# Main.net
KiCad netlist of a schematic drawn in Altium Designer
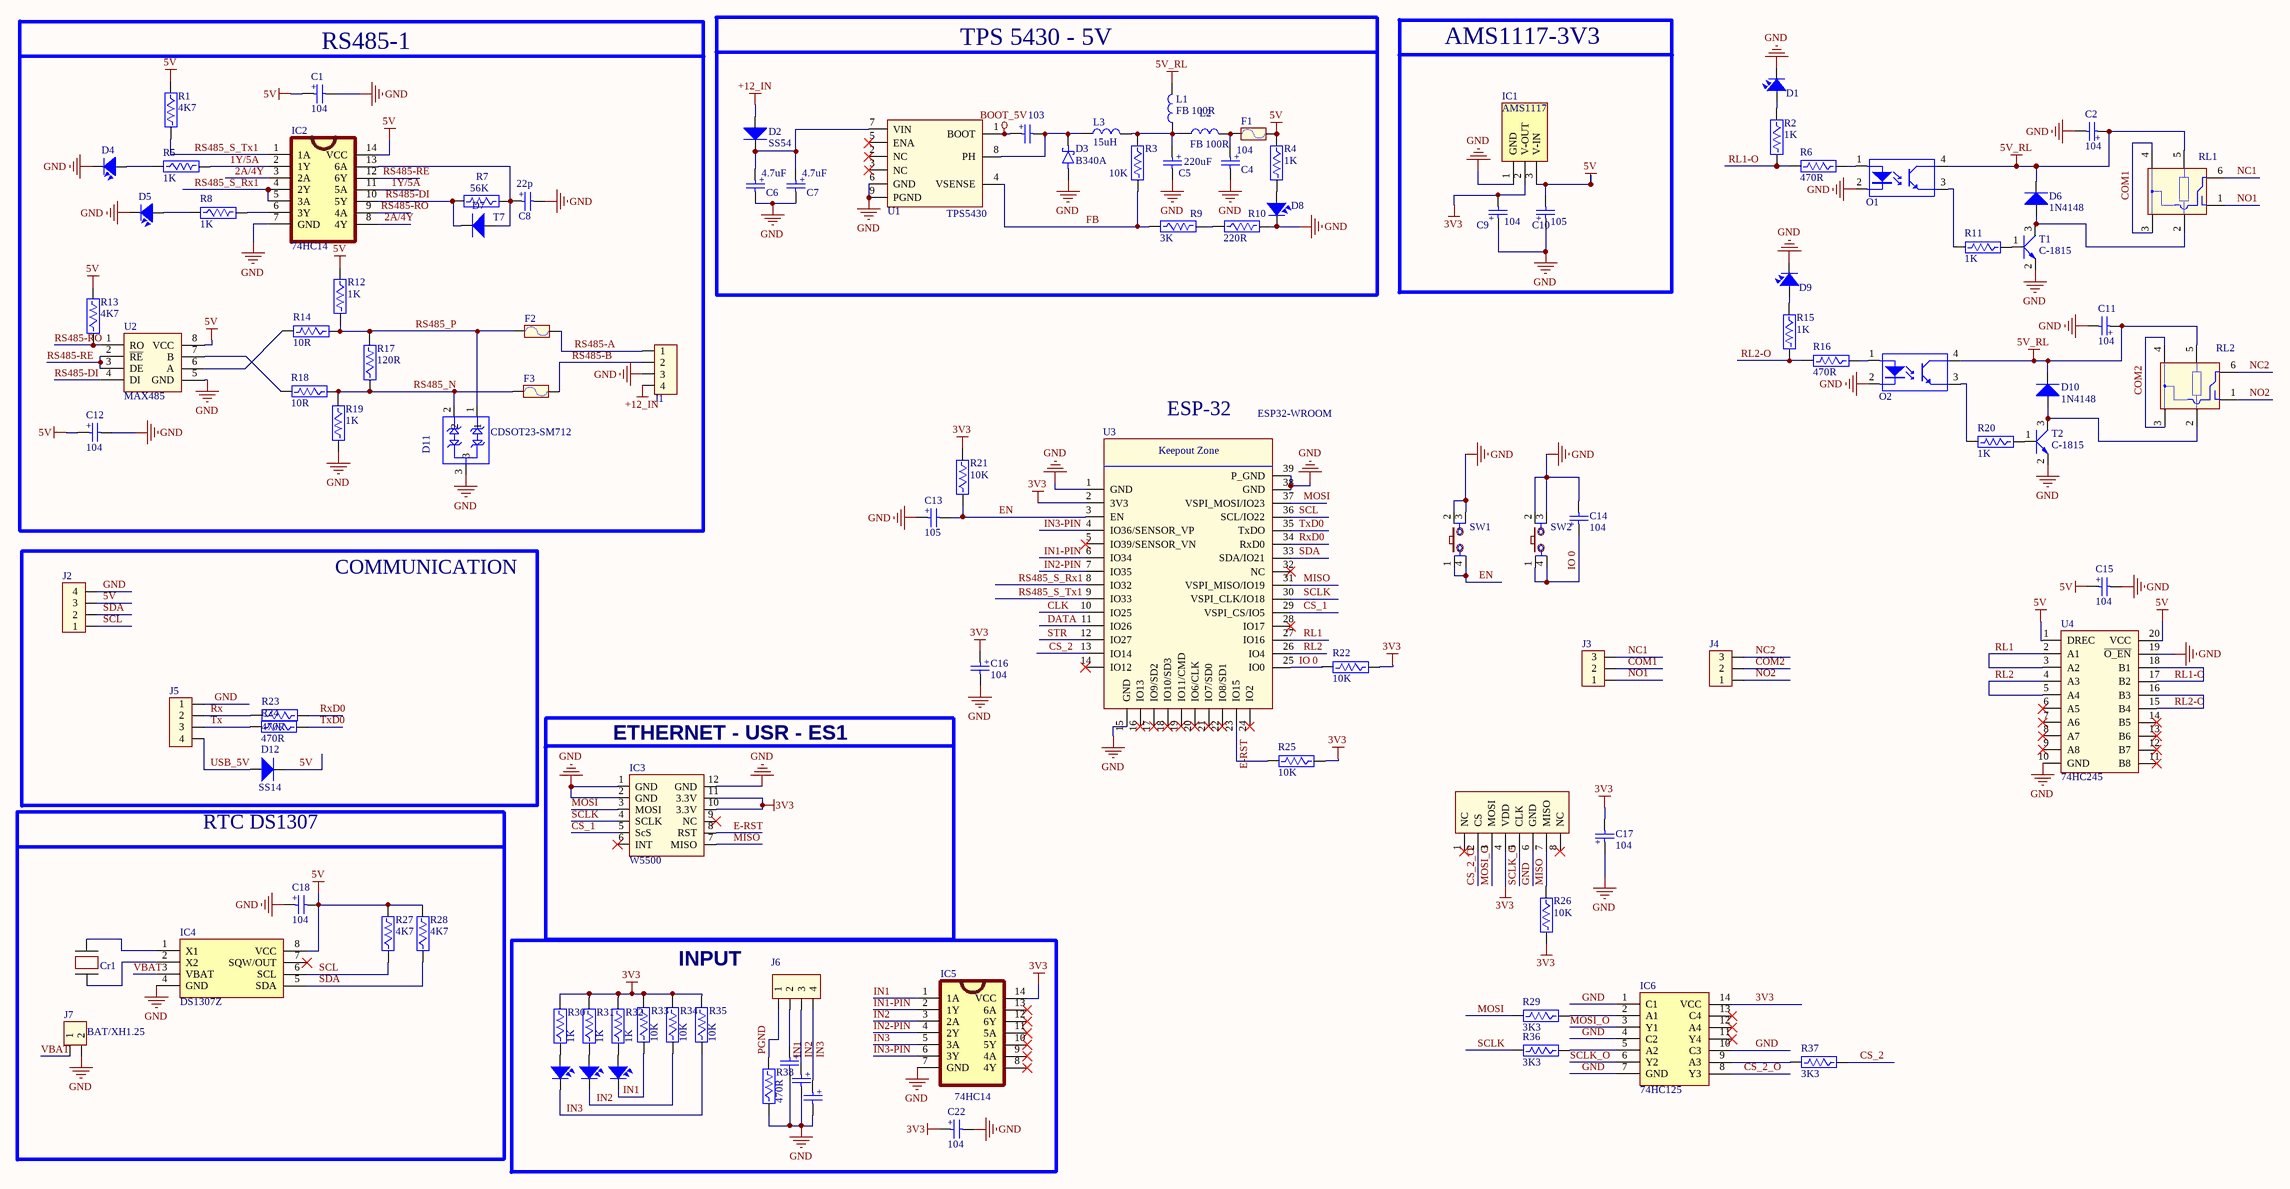
[diagram p0: Main.SchDoc]

(export (version "E")
  (design (tool "Eeschema 10.0.6"))
  (components
    (comp (ref "C1") (value "104") (footprint "CAP 0805") (libsource (lib "Silver Sch") (part "Capacitor")))
    (comp (ref "C2") (value "104") (footprint "CAP 0805") (libsource (lib "Silver Sch") (part "Capacitor")))
    (comp (ref "C3") (value "103") (footprint "CAP 0805") (libsource (lib "Silver Sch") (part "Capacitor")))
    (comp (ref "C4") (value "104") (footprint "CAP 0805") (libsource (lib "Silver Sch") (part "Capacitor")))
    (comp (ref "C5")
      (value "220uF")
      (footprint "Capacitor 6x11")
      (libsource (lib "Silver Sch") (part "Capacitor"))
    )
    (comp (ref "C6") (value "4.7uF") (footprint "CAP 0805") (libsource (lib "Silver Sch") (part "Capacitor")))
    (comp (ref "C7") (value "4.7uF") (footprint "CAP 0805") (libsource (lib "Silver Sch") (part "Capacitor")))
    (comp (ref "C8") (value "22p") (footprint "CAP 0805") (libsource (lib "Silver Sch") (part "Capacitor")))
    (comp (ref "C9") (value "104") (footprint "CAP 0805") (libsource (lib "Silver Sch") (part "Capacitor")))
    (comp (ref "C10") (value "105") (footprint "CAP 0805") (libsource (lib "Silver Sch") (part "Capacitor")))
    (comp (ref "C11") (value "104") (footprint "CAP 0805") (libsource (lib "Silver Sch") (part "Capacitor")))
    (comp (ref "C12") (value "104") (footprint "CAP 0805") (libsource (lib "Silver Sch") (part "Capacitor")))
    (comp (ref "C13") (value "105") (footprint "CAP 0805") (libsource (lib "Silver Sch") (part "Capacitor")))
    (comp (ref "C14") (value "104") (footprint "CAP 0805") (libsource (lib "Silver Sch") (part "Capacitor")))
    (comp (ref "C15") (value "104") (footprint "CAP 0805") (libsource (lib "Silver Sch") (part "Capacitor")))
    (comp (ref "C16") (value "104") (footprint "CAP 0805") (libsource (lib "Silver Sch") (part "Capacitor")))
    (comp (ref "C17") (value "104") (footprint "CAP 0805") (libsource (lib "Silver Sch") (part "Capacitor")))
    (comp (ref "C18") (value "104") (footprint "CAP 0805") (libsource (lib "Silver Sch") (part "Capacitor")))
    (comp (ref "C19") (value "104") (footprint "CAP 0805") (libsource (lib "Silver Sch") (part "Capacitor")))
    (comp (ref "C20") (value "104") (footprint "CAP 0805") (libsource (lib "Silver Sch") (part "Capacitor")))
    (comp (ref "C21") (value "104") (footprint "CAP 0805") (libsource (lib "Silver Sch") (part "Capacitor")))
    (comp (ref "C22") (value "104") (footprint "CAP 0805") (libsource (lib "Silver Sch") (part "Capacitor")))
    (comp (ref "Cr1")
      (value "FC135")
      (footprint "FC135327680KAAG0")
      (libsource (lib "Silver Sch") (part "Crystal"))
    )
    (comp (ref "D1")
      (value "LED RED 0805")
      (footprint "LED SMD 0805")
      (libsource (lib "Silver Sch") (part "Led Smd"))
    )
    (comp (ref "D2") (value "SS54") (footprint "Diode SMB") (libsource (lib "Silver Sch") (part "Diode")))
    (comp (ref "D3")
      (value "B340A")
      (footprint "Diode Schotky")
      (libsource (lib "Silver Sch") (part "Diode schottky"))
    )
    (comp (ref "D4")
      (value "LED RED 0805")
      (footprint "LED SMD 0805")
      (libsource (lib "Silver Sch") (part "Led Smd"))
    )
    (comp (ref "D5")
      (value "LED RED 0805")
      (footprint "LED SMD 0805")
      (libsource (lib "Silver Sch") (part "Led Smd"))
    )
    (comp (ref "D6") (value "1N4148") (footprint "1N4848") (libsource (lib "Silver Sch") (part "1N4148")))
    (comp (ref "D7") (value "T7") (footprint "Diode SMD") (libsource (lib "Silver Sch") (part "Diode")))
    (comp (ref "D8")
      (value "LED RED 0805")
      (footprint "LED SMD 0805")
      (libsource (lib "Silver Sch") (part "Led Smd"))
    )
    (comp (ref "D9")
      (value "LED RED 0805")
      (footprint "LED SMD 0805")
      (libsource (lib "Silver Sch") (part "Led Smd"))
    )
    (comp (ref "D10") (value "1N4148") (footprint "1N4848") (libsource (lib "Silver Sch") (part "1N4148")))
    (comp (ref "D11")
      (value "SM712")
      (footprint "SOT-23-3")
      (description "TVS-DIODE;BIR-DIR,DUAL,400W,7.5V,SOT23,CDSOT23-SM712")
      (fields (field (name "M1_VALUE") "CDSOT23-SM712"))
      (libsource (lib "NS16-001650") (part "TVS-CDSOT23-SM712"))
    )
    (comp (ref "D12") (value "SS14") (footprint "Diode SMB") (libsource (lib "Silver Sch") (part "Diode")))
    (comp (ref "D13")
      (value "LED RED 0805")
      (footprint "LED SMD 0805")
      (libsource (lib "Silver Sch") (part "Led Smd"))
    )
    (comp (ref "D14")
      (value "LED RED 0805")
      (footprint "LED SMD 0805")
      (libsource (lib "Silver Sch") (part "Led Smd"))
    )
    (comp (ref "D15")
      (value "LED RED 0805")
      (footprint "LED SMD 0805")
      (libsource (lib "Silver Sch") (part "Led Smd"))
    )
    (comp (ref "F1")
      (value "Fuse 1812/6V")
      (footprint "fuse 1812")
      (libsource (lib "Silver Sch") (part "Fuse"))
    )
    (comp (ref "F2")
      (value "Fuse 0805/15V")
      (footprint "Fuse-0805")
      (libsource (lib "Silver Sch") (part "Fuse"))
    )
    (comp (ref "F3")
      (value "Fuse 0805/15V")
      (footprint "Fuse-0805")
      (libsource (lib "Silver Sch") (part "Fuse"))
    )
    (comp (ref "IC1")
      (value "ASM1117/3V3")
      (footprint "ASM1117")
      (libsource (lib "Silver Sch") (part "AMS1117"))
    )
    (comp (ref "IC2") (value "74HC14") (footprint "SOP14") (libsource (lib "Silver Sch") (part "74HC14")))
    (comp (ref "IC3")
      (value "W5500")
      (footprint "W5500-USR-ES1")
      (libsource (lib "Silver Sch") (part "W5500-USR-ES1"))
    )
    (comp (ref "IC4")
      (value "DS1307Z")
      (footprint "SamacSys:SOIC127P600X175-8N")
      (description "Integrated Circuit")
      (fields (field (name "MOUSER PART NUMBER") "700-DS1307Z-NR"))
      (libsource (lib "SamacSys") (part "DS1307Z"))
    )
    (comp (ref "IC5") (value "74HC14") (footprint "SOP14") (libsource (lib "Silver Sch") (part "74hc14")))
    (comp (ref "IC6")
      (value "74HC125")
      (footprint "SamacSys:SOP65P640X120-14N")
      (description "Integrated Circuit")
      (fields
        (field (name "MANUFACTURER_PART_NUMBER") "MM74HC125MTCX")
        (field (name "MOUSER PART NUMBER") "512-MM74HC125MTCX")
      )
      (libsource (lib "SamacSys") (part "MM74HC125MTCX"))
    )
    (comp (ref "J1")
      (value "KF128-5.08-4P")
      (footprint "CON 4 KF128 5.08")
      (libsource (lib "") (part "Con4_1"))
    )
    (comp (ref "J2")
      (value "XH2.54-4P-C")
      (footprint "XH-2.54 4P-T")
      (libsource (lib "Silver Sch") (part "Header 4P"))
    )
    (comp (ref "J3")
      (value "KF128 5.08-3P")
      (footprint "CON KF128-3P")
      (libsource (lib "Silver Sch") (part "Con3"))
    )
    (comp (ref "J4")
      (value "KF128 5.08-3P")
      (footprint "CON KF128-3P")
      (libsource (lib "Silver Sch") (part "Con3"))
    )
    (comp (ref "J5")
      (value "XH2.54-4P-C")
      (footprint "XH-2.54 4P-C")
      (libsource (lib "") (part "Header 4P_1"))
    )
    (comp (ref "J6")
      (value "KF128-5.08-4P")
      (footprint "CON 4 KF128 5.08")
      (libsource (lib "Silver Sch") (part "Con4"))
    )
    (comp (ref "J7")
      (value "BAT/XH1.25")
      (footprint "Header 1.25")
      (libsource (lib "Silver Sch") (part "Con2"))
    )
    (comp (ref "L1")
      (value "FB 100R")
      (footprint "L-Inductor 0805")
      (libsource (lib "Silver Sch") (part "L-Inductor"))
    )
    (comp (ref "L2")
      (value "FB 100R")
      (footprint "L-Inductor 0805")
      (libsource (lib "Silver Sch") (part "L-Inductor"))
    )
    (comp (ref "L3")
      (value "15uH")
      (footprint "Inductor CD75")
      (libsource (lib "Silver Sch") (part "L-Inductor"))
    )
    (comp (ref "Mini SDCard1")
      (value "SD?")
      (footprint "Mini SDCard")
      (libsource (lib "Silver Sch") (part "Mini SDCard"))
    )
    (comp (ref "O1")
      (value "EL3H7")
      (footprint "SOIC127P700X200-4N")
      (libsource (lib "Silver Sch") (part "EL3H7"))
    )
    (comp (ref "O2")
      (value "EL3H7")
      (footprint "SOIC127P700X200-4N")
      (libsource (lib "Silver Sch") (part "EL3H7"))
    )
    (comp (ref "R1") (value "4K7") (footprint "Res 0805") (libsource (lib "Silver Sch") (part "Res")))
    (comp (ref "R2") (value "1K") (footprint "Res 0805") (libsource (lib "Silver Sch") (part "Res")))
    (comp (ref "R3") (value "10K") (footprint "Res 0805") (libsource (lib "Silver Sch") (part "Res")))
    (comp (ref "R4") (value "1K") (footprint "Res 0805") (libsource (lib "Silver Sch") (part "Res")))
    (comp (ref "R5") (value "1K") (footprint "Res 0805") (libsource (lib "Silver Sch") (part "Res")))
    (comp (ref "R6") (value "470R") (footprint "Res 0805") (libsource (lib "Silver Sch") (part "Res")))
    (comp (ref "R7") (value "56K") (footprint "Res 0805") (libsource (lib "Silver Sch") (part "Res")))
    (comp (ref "R8") (value "1K") (footprint "Res 0805") (libsource (lib "Silver Sch") (part "Res")))
    (comp (ref "R9") (value "3K") (footprint "Res 0805") (libsource (lib "Silver Sch") (part "Res")))
    (comp (ref "R10") (value "220R") (footprint "Res 0805") (libsource (lib "Silver Sch") (part "Res")))
    (comp (ref "R11") (value "1K") (footprint "Res 0805") (libsource (lib "Silver Sch") (part "Res")))
    (comp (ref "R12") (value "1K") (footprint "Res 0805") (libsource (lib "Silver Sch") (part "Res")))
    (comp (ref "R13") (value "4K7") (footprint "Res 0805") (libsource (lib "Silver Sch") (part "Res")))
    (comp (ref "R14") (value "10R") (footprint "Res 0805") (libsource (lib "Silver Sch") (part "Res")))
    (comp (ref "R15") (value "1K") (footprint "Res 0805") (libsource (lib "Silver Sch") (part "Res")))
    (comp (ref "R16") (value "470R") (footprint "Res 0805") (libsource (lib "Silver Sch") (part "Res")))
    (comp (ref "R17") (value "120R") (footprint "Res 0805") (libsource (lib "Silver Sch") (part "Res")))
    (comp (ref "R18") (value "10R") (footprint "Res 0805") (libsource (lib "Silver Sch") (part "Res")))
    (comp (ref "R19") (value "1K") (footprint "Res 0805") (libsource (lib "Silver Sch") (part "Res")))
    (comp (ref "R20") (value "1K") (footprint "Res 0805") (libsource (lib "Silver Sch") (part "Res")))
    (comp (ref "R21") (value "10K") (footprint "Res 0805") (libsource (lib "Silver Sch") (part "Res")))
    (comp (ref "R22") (value "10K") (footprint "Res 0805") (libsource (lib "Silver Sch") (part "Res")))
    (comp (ref "R23") (value "470R") (footprint "Res 0805") (libsource (lib "Silver Sch") (part "Res")))
    (comp (ref "R24") (value "470R") (footprint "Res 0805") (libsource (lib "Silver Sch") (part "Res")))
    (comp (ref "R25") (value "10K") (footprint "Res 0805") (libsource (lib "Silver Sch") (part "Res")))
    (comp (ref "R26") (value "10K") (footprint "Res 0805") (libsource (lib "Silver Sch") (part "Res")))
    (comp (ref "R27") (value "4K7") (footprint "Res 0805") (libsource (lib "Silver Sch") (part "Res")))
    (comp (ref "R28") (value "4K7") (footprint "Res 0805") (libsource (lib "Silver Sch") (part "Res")))
    (comp (ref "R29") (value "3K3") (footprint "Res 0805") (libsource (lib "Silver Sch") (part "Res")))
    (comp (ref "R30") (value "1K") (footprint "Res 0805") (libsource (lib "Silver Sch") (part "Res")))
    (comp (ref "R31") (value "1K") (footprint "Res 0805") (libsource (lib "Silver Sch") (part "Res")))
    (comp (ref "R32") (value "1K") (footprint "Res 0805") (libsource (lib "Silver Sch") (part "Res")))
    (comp (ref "R33") (value "10K") (footprint "Res 0805") (libsource (lib "Silver Sch") (part "Res")))
    (comp (ref "R34") (value "10K") (footprint "Res 0805") (libsource (lib "Silver Sch") (part "Res")))
    (comp (ref "R35") (value "10K") (footprint "Res 0805") (libsource (lib "Silver Sch") (part "Res")))
    (comp (ref "R36") (value "3K3") (footprint "Res 0805") (libsource (lib "Silver Sch") (part "Res")))
    (comp (ref "R37") (value "3K3") (footprint "Res 0805") (libsource (lib "Silver Sch") (part "Res")))
    (comp (ref "R38") (value "470R") (footprint "Res 0805") (libsource (lib "Silver Sch") (part "Res")))
    (comp (ref "RL1")
      (value "Relay-HK4100F/12V")
      (footprint "HK4100FDC5VSHG")
      (libsource (lib "Silver Sch") (part "Relay-HK4100F"))
    )
    (comp (ref "RL2")
      (value "Relay-HK4100F/12V")
      (footprint "HK4100FDC5VSHG")
      (libsource (lib "Silver Sch") (part "Relay-HK4100F"))
    )
    (comp (ref "SW1")
      (value "SW")
      (footprint "SW2-SMD")
      (description "Switch button 4 pin")
      (libsource (lib "LIBRARY") (part "SW4"))
    )
    (comp (ref "SW2")
      (value "SW")
      (footprint "SW2-SMD")
      (description "Switch button 4 pin")
      (libsource (lib "LIBRARY") (part "SW4"))
    )
    (comp (ref "T1") (value "C-1815") (footprint "SOT23") (libsource (lib "Silver Sch") (part "Tranzitor")))
    (comp (ref "T2") (value "C-1815") (footprint "SOT23") (libsource (lib "Silver Sch") (part "Tranzitor")))
    (comp (ref "U1")
      (value "TPS5430")
      (footprint "SOIC127P600X170-9N")
      (libsource (lib "Silver Sch") (part "TPS5430"))
    )
    (comp (ref "U2")
      (value "MAX485")
      (footprint "MAX485  SOP8")
      (libsource (lib "Silver Sch") (part "MAX485"))
    )
    (comp (ref "U3")
      (value "ESP32-WROOM")
      (footprint "ESP32WROOM32UEM113EH2800UH3Q0")
      (libsource (lib "Silver Sch") (part "ESP32-WROOM"))
    )
    (comp (ref "U4")
      (value "74HC245")
      (footprint "74HC245-TSSOP20-4.4mm")
      (libsource (lib "Silver Sch") (part "74HC245"))
    )
  )
  (nets
    (net (code "1") (name "+12_IN") (class "Default")
      (node (ref "D2") (pin "1") (pinfunction "A_1") (pintype "passive"))
      (node (ref "J1") (pin "4") (pinfunction "4_4") (pintype "passive"))
    )
    (net (code "2") (name "/1Y{slash}5A") (class "Default")
      (node (ref "IC2") (pin "11") (pinfunction "5A_11") (pintype "passive"))
      (node (ref "IC2") (pin "2") (pinfunction "1Y_2") (pintype "passive"))
      (node (ref "R5") (pin "2") (pinfunction "2_2") (pintype "passive"))
    )
    (net (code "3") (name "/2A{slash}4Y") (class "Default")
      (node (ref "IC2") (pin "3") (pinfunction "2A_3") (pintype "passive"))
      (node (ref "IC2") (pin "8") (pinfunction "4Y_8") (pintype "passive"))
    )
    (net (code "4") (name "/CLK") (class "Default")
      (node (ref "U3") (pin "10") (pinfunction "IO25_10") (pintype "passive"))
    )
    (net (code "5") (name "/COM1") (class "Default")
      (node (ref "J3") (pin "2") (pinfunction "2_2") (pintype "passive"))
      (node (ref "RL1") (pin "3") (pinfunction "COM_3") (pintype "passive"))
      (node (ref "RL1") (pin "4") (pinfunction "COM_4") (pintype "passive"))
    )
    (net (code "6") (name "/COM2") (class "Default")
      (node (ref "J4") (pin "2") (pinfunction "2_2") (pintype "passive"))
      (node (ref "RL2") (pin "3") (pinfunction "COM_3") (pintype "passive"))
      (node (ref "RL2") (pin "4") (pinfunction "COM_4") (pintype "passive"))
    )
    (net (code "7") (name "/CS_1") (class "Default")
      (node (ref "IC3") (pin "5") (pinfunction "ScS_5") (pintype "passive"))
      (node (ref "U3") (pin "29") (pinfunction "VSPI_CS/IO5_29") (pintype "passive"))
    )
    (net (code "8") (name "/CS_2") (class "Default")
      (node (ref "R37") (pin "1") (pinfunction "1_1") (pintype "passive"))
      (node (ref "U3") (pin "13") (pinfunction "IO14_13") (pintype "passive"))
    )
    (net (code "9") (name "/CS_2_O") (class "Default")
      (node (ref "IC6") (pin "8") (pinfunction "Y3_8") (pintype "passive"))
      (node (ref "Mini SDCard1") (pin "2") (pinfunction "CS_2") (pintype "passive"))
    )
    (net (code "10") (name "/DATA") (class "Default")
      (node (ref "U3") (pin "11") (pinfunction "IO26_11") (pintype "passive"))
    )
    (net (code "11") (name "/E-RST") (class "Default")
      (node (ref "IC3") (pin "8") (pinfunction "RST_8") (pintype "passive"))
      (node (ref "R25") (pin "2") (pinfunction "2_2") (pintype "passive"))
      (node (ref "U3") (pin "23") (pinfunction "IO15_23") (pintype "passive"))
    )
    (net (code "12") (name "/EN") (class "Default")
      (node (ref "C13") (pin "2") (pinfunction "2_2") (pintype "passive"))
      (node (ref "R21") (pin "1") (pinfunction "1_1") (pintype "passive"))
      (node (ref "SW1") (pin "1") (pintype "passive"))
      (node (ref "SW1") (pin "4") (pinfunction "4_4") (pintype "passive"))
      (node (ref "U3") (pin "3") (pinfunction "EN_3") (pintype "passive"))
    )
    (net (code "13") (name "/FB") (class "Default")
      (node (ref "R3") (pin "2") (pinfunction "2_2") (pintype "passive"))
      (node (ref "R9") (pin "1") (pinfunction "1_1") (pintype "passive"))
      (node (ref "U1") (pin "4") (pinfunction "VSENSE_4") (pintype "passive"))
    )
    (net (code "14") (name "/IN1") (class "Default")
      (node (ref "C19") (pin "1") (pinfunction "1_1") (pintype "passive"))
      (node (ref "D15") (pin "2") (pinfunction "2_2") (pintype "passive"))
      (node (ref "IC5") (pin "1") (pinfunction "1A_1") (pintype "passive"))
      (node (ref "J6") (pin "2") (pinfunction "2_2") (pintype "passive"))
      (node (ref "R33") (pin "1") (pinfunction "1_1") (pintype "passive"))
    )
    (net (code "15") (name "/IN1-PIN") (class "Default")
      (node (ref "IC5") (pin "2") (pinfunction "1Y_2") (pintype "passive"))
      (node (ref "U3") (pin "6") (pinfunction "IO34_6") (pintype "passive"))
    )
    (net (code "16") (name "/IN2") (class "Default")
      (node (ref "C20") (pin "1") (pinfunction "1_1") (pintype "passive"))
      (node (ref "D14") (pin "2") (pinfunction "2_2") (pintype "passive"))
      (node (ref "IC5") (pin "3") (pinfunction "2A_3") (pintype "passive"))
      (node (ref "J6") (pin "3") (pinfunction "3_3") (pintype "passive"))
      (node (ref "R34") (pin "1") (pinfunction "1_1") (pintype "passive"))
    )
    (net (code "17") (name "/IN2-PIN") (class "Default")
      (node (ref "IC5") (pin "4") (pinfunction "2Y_4") (pintype "passive"))
      (node (ref "U3") (pin "7") (pinfunction "IO35_7") (pintype "passive"))
    )
    (net (code "18") (name "/IN3") (class "Default")
      (node (ref "C21") (pin "1") (pinfunction "1_1") (pintype "passive"))
      (node (ref "D13") (pin "2") (pinfunction "2_2") (pintype "passive"))
      (node (ref "IC5") (pin "5") (pinfunction "3A_5") (pintype "passive"))
      (node (ref "J6") (pin "4") (pinfunction "4_4") (pintype "passive"))
      (node (ref "R35") (pin "1") (pinfunction "1_1") (pintype "passive"))
    )
    (net (code "19") (name "/IN3-PIN") (class "Default")
      (node (ref "IC5") (pin "6") (pinfunction "3Y_6") (pintype "passive"))
      (node (ref "U3") (pin "4") (pinfunction "IO36/SENSOR_VP_4") (pintype "passive"))
    )
    (net (code "20") (name "/IO 0") (class "Default")
      (node (ref "C14") (pin "1") (pinfunction "1_1") (pintype "passive"))
      (node (ref "R22") (pin "2") (pinfunction "2_2") (pintype "passive"))
      (node (ref "SW2") (pin "1") (pintype "passive"))
      (node (ref "SW2") (pin "4") (pinfunction "4_4") (pintype "passive"))
      (node (ref "U3") (pin "25") (pinfunction "IO0_25") (pintype "passive"))
    )
    (net (code "21") (name "/MISO") (class "Default")
      (node (ref "IC3") (pin "7") (pinfunction "MISO_7") (pintype "passive"))
      (node (ref "Mini SDCard1") (pin "7") (pinfunction "MISO_7") (pintype "passive"))
      (node (ref "R26") (pin "1") (pinfunction "1_1") (pintype "passive"))
      (node (ref "U3") (pin "31") (pinfunction "VSPI_MISO/IO19_31") (pintype "passive"))
    )
    (net (code "22") (name "/MOSI") (class "Default")
      (node (ref "IC3") (pin "3") (pinfunction "MOSI_3") (pintype "passive"))
      (node (ref "R29") (pin "2") (pinfunction "2_2") (pintype "passive"))
      (node (ref "U3") (pin "37") (pinfunction "VSPI_MOSI/IO23_37") (pintype "passive"))
    )
    (net (code "23") (name "/MOSI_O") (class "Default")
      (node (ref "IC6") (pin "3") (pinfunction "Y1_3") (pintype "passive"))
      (node (ref "Mini SDCard1") (pin "3") (pinfunction "MOSI_3") (pintype "passive"))
    )
    (net (code "24") (name "/NC1") (class "Default")
      (node (ref "J3") (pin "3") (pinfunction "3_3") (pintype "passive"))
      (node (ref "RL1") (pin "6") (pinfunction "NO_6") (pintype "passive"))
    )
    (net (code "25") (name "/NC2") (class "Default")
      (node (ref "J4") (pin "3") (pinfunction "3_3") (pintype "passive"))
      (node (ref "RL2") (pin "6") (pinfunction "NO_6") (pintype "passive"))
    )
    (net (code "26") (name "/NO1") (class "Default")
      (node (ref "J3") (pin "1") (pinfunction "1_1") (pintype "passive"))
      (node (ref "RL1") (pin "1") (pinfunction "NC_1") (pintype "passive"))
    )
    (net (code "27") (name "/NO2") (class "Default")
      (node (ref "J4") (pin "1") (pinfunction "1_1") (pintype "passive"))
      (node (ref "RL2") (pin "1") (pinfunction "NC_1") (pintype "passive"))
    )
    (net (code "28") (name "/PGND") (class "Default")
      (node (ref "J6") (pin "1") (pinfunction "1_1") (pintype "passive"))
      (node (ref "R38") (pin "2") (pinfunction "2_2") (pintype "passive"))
    )
    (net (code "29") (name "/RL1") (class "Default")
      (node (ref "U3") (pin "27") (pinfunction "IO16_27") (pintype "passive"))
      (node (ref "U4") (pin "2") (pinfunction "A1_2") (pintype "passive"))
      (node (ref "U4") (pin "3") (pinfunction "A2_3") (pintype "passive"))
    )
    (net (code "30") (name "/RL1-O") (class "Default")
      (node (ref "R2") (pin "2") (pinfunction "2_2") (pintype "passive"))
      (node (ref "R6") (pin "2") (pinfunction "2_2") (pintype "passive"))
      (node (ref "U4") (pin "17") (pinfunction "B2_17") (pintype "passive"))
      (node (ref "U4") (pin "18") (pinfunction "B1_18") (pintype "passive"))
    )
    (net (code "31") (name "/RL2") (class "Default")
      (node (ref "U3") (pin "26") (pinfunction "IO4_26") (pintype "passive"))
      (node (ref "U4") (pin "4") (pinfunction "A3_4") (pintype "passive"))
      (node (ref "U4") (pin "5") (pinfunction "A4_5") (pintype "passive"))
    )
    (net (code "32") (name "/RL2-O") (class "Default")
      (node (ref "R15") (pin "2") (pinfunction "2_2") (pintype "passive"))
      (node (ref "R16") (pin "2") (pinfunction "2_2") (pintype "passive"))
      (node (ref "U4") (pin "15") (pinfunction "B4_15") (pintype "passive"))
      (node (ref "U4") (pin "16") (pinfunction "B3_16") (pintype "passive"))
    )
    (net (code "33") (name "/RS485-A") (class "Default")
      (node (ref "F2") (pin "2") (pinfunction "2_2") (pintype "passive"))
      (node (ref "J1") (pin "1") (pinfunction "1_1") (pintype "passive"))
    )
    (net (code "34") (name "/RS485-B") (class "Default")
      (node (ref "F3") (pin "2") (pinfunction "2_2") (pintype "passive"))
      (node (ref "J1") (pin "2") (pinfunction "2_2") (pintype "passive"))
    )
    (net (code "35") (name "/RS485-DI") (class "Default")
      (node (ref "D7") (pin "2") (pinfunction "K_2") (pintype "passive"))
      (node (ref "IC2") (pin "10") (pinfunction "5Y_10") (pintype "passive"))
      (node (ref "R7") (pin "2") (pinfunction "2_2") (pintype "passive"))
      (node (ref "U2") (pin "4") (pinfunction "DI_4") (pintype "passive"))
    )
    (net (code "36") (name "/RS485-RE") (class "Default")
      (node (ref "IC2") (pin "12") (pinfunction "6Y_12") (pintype "passive"))
      (node (ref "U2") (pin "2") (pinfunction "~{RE}_2") (pintype "passive"))
      (node (ref "U2") (pin "3") (pinfunction "DE_3") (pintype "passive"))
    )
    (net (code "37") (name "/RS485-RO") (class "Default")
      (node (ref "IC2") (pin "9") (pinfunction "4A_9") (pintype "passive"))
      (node (ref "R13") (pin "1") (pinfunction "1_1") (pintype "passive"))
      (node (ref "U2") (pin "1") (pinfunction "RO_1") (pintype "passive"))
    )
    (net (code "38") (name "/RS485_N") (class "Default")
      (node (ref "D11") (pin "2") (pinfunction "2_2") (pintype "passive"))
      (node (ref "F3") (pin "1") (pinfunction "1_1") (pintype "passive"))
      (node (ref "R17") (pin "1") (pinfunction "1_1") (pintype "passive"))
      (node (ref "R18") (pin "1") (pinfunction "1_1") (pintype "passive"))
      (node (ref "R19") (pin "1") (pinfunction "1_1") (pintype "passive"))
    )
    (net (code "39") (name "/RS485_P") (class "Default")
      (node (ref "D11") (pin "1") (pinfunction "1_1") (pintype "passive"))
      (node (ref "F2") (pin "1") (pinfunction "1_1") (pintype "passive"))
      (node (ref "R12") (pin "2") (pinfunction "2_2") (pintype "passive"))
      (node (ref "R14") (pin "1") (pinfunction "1_1") (pintype "passive"))
      (node (ref "R17") (pin "2") (pinfunction "2_2") (pintype "passive"))
    )
    (net (code "40") (name "/RS485_S_Rx1") (class "Default")
      (node (ref "IC2") (pin "4") (pinfunction "2Y_4") (pintype "passive"))
      (node (ref "IC2") (pin "5") (pinfunction "3A_5") (pintype "passive"))
      (node (ref "U3") (pin "8") (pinfunction "IO32_8") (pintype "passive"))
    )
    (net (code "41") (name "/RS485_S_Tx1") (class "Default")
      (node (ref "IC2") (pin "1") (pinfunction "1A_1") (pintype "passive"))
      (node (ref "R1") (pin "2") (pinfunction "2_2") (pintype "passive"))
      (node (ref "U3") (pin "9") (pinfunction "IO33_9") (pintype "passive"))
    )
    (net (code "42") (name "/Rx") (class "Default")
      (node (ref "J5") (pin "2") (pinfunction "2_2") (pintype "passive"))
      (node (ref "R23") (pin "2") (pinfunction "2_2") (pintype "passive"))
    )
    (net (code "43") (name "/RxD0") (class "Default")
      (node (ref "R23") (pin "1") (pinfunction "1_1") (pintype "passive"))
      (node (ref "U3") (pin "34") (pinfunction "RxD0_34") (pintype "passive"))
    )
    (net (code "44") (name "/SCL") (class "Default")
      (node (ref "IC4") (pin "6") (pinfunction "SCL_6") (pintype "passive"))
      (node (ref "J2") (pin "1") (pinfunction "1_1") (pintype "passive"))
      (node (ref "R27") (pin "1") (pinfunction "1_1") (pintype "passive"))
      (node (ref "U3") (pin "36") (pinfunction "SCL/IO22_36") (pintype "passive"))
    )
    (net (code "45") (name "/SCLK") (class "Default")
      (node (ref "IC3") (pin "4") (pinfunction "SCLK_4") (pintype "passive"))
      (node (ref "R36") (pin "2") (pinfunction "2_2") (pintype "passive"))
      (node (ref "U3") (pin "30") (pinfunction "VSPI_CLK/IO18_30") (pintype "passive"))
    )
    (net (code "46") (name "/SCLK_O") (class "Default")
      (node (ref "IC6") (pin "6") (pinfunction "Y2_6") (pintype "passive"))
      (node (ref "Mini SDCard1") (pin "5") (pinfunction "CLK_5") (pintype "passive"))
    )
    (net (code "47") (name "/SDA") (class "Default")
      (node (ref "IC4") (pin "5") (pinfunction "SDA_5") (pintype "passive"))
      (node (ref "J2") (pin "2") (pinfunction "2_2") (pintype "passive"))
      (node (ref "R28") (pin "1") (pinfunction "1_1") (pintype "passive"))
      (node (ref "U3") (pin "33") (pinfunction "SDA/IO21_33") (pintype "passive"))
    )
    (net (code "48") (name "/STR") (class "Default")
      (node (ref "U3") (pin "12") (pinfunction "IO27_12") (pintype "passive"))
    )
    (net (code "49") (name "/Tx") (class "Default")
      (node (ref "J5") (pin "3") (pinfunction "3_3") (pintype "passive"))
      (node (ref "R24") (pin "2") (pinfunction "2_2") (pintype "passive"))
    )
    (net (code "50") (name "/TxD0") (class "Default")
      (node (ref "R24") (pin "1") (pinfunction "1_1") (pintype "passive"))
      (node (ref "U3") (pin "35") (pinfunction "TxDO_35") (pintype "passive"))
    )
    (net (code "51") (name "/USB_5V") (class "Default")
      (node (ref "D12") (pin "1") (pinfunction "A_1") (pintype "passive"))
      (node (ref "J5") (pin "4") (pinfunction "4_4") (pintype "passive"))
    )
    (net (code "52") (name "/VBAT") (class "Default")
      (node (ref "IC4") (pin "3") (pinfunction "VBAT_3") (pintype "passive"))
      (node (ref "J7") (pin "1") (pinfunction "1_1") (pintype "passive"))
    )
    (net (code "53") (name "3V3") (class "Default")
      (node (ref "C16") (pin "1") (pinfunction "1_1") (pintype "passive"))
      (node (ref "C17") (pin "2") (pinfunction "2_2") (pintype "passive"))
      (node (ref "C22") (pin "1") (pinfunction "1_1") (pintype "passive"))
      (node (ref "C9") (pin "2") (pinfunction "2_2") (pintype "passive"))
      (node (ref "IC1") (pin "2") (pinfunction "V-OUT_2") (pintype "power_in"))
      (node (ref "IC3") (pin "10") (pinfunction "3.3V_10") (pintype "passive"))
      (node (ref "IC3") (pin "11") (pinfunction "3.3V_11") (pintype "passive"))
      (node (ref "IC5") (pin "14") (pinfunction "VCC_14") (pintype "passive"))
      (node (ref "IC6") (pin "14") (pinfunction "VCC_14") (pintype "passive"))
      (node (ref "Mini SDCard1") (pin "4") (pinfunction "VDD_4") (pintype "passive"))
      (node (ref "R21") (pin "2") (pinfunction "2_2") (pintype "passive"))
      (node (ref "R22") (pin "1") (pinfunction "1_1") (pintype "passive"))
      (node (ref "R25") (pin "1") (pinfunction "1_1") (pintype "passive"))
      (node (ref "R26") (pin "2") (pinfunction "2_2") (pintype "passive"))
      (node (ref "R30") (pin "2") (pinfunction "2_2") (pintype "passive"))
      (node (ref "R31") (pin "2") (pinfunction "2_2") (pintype "passive"))
      (node (ref "R32") (pin "2") (pinfunction "2_2") (pintype "passive"))
      (node (ref "R33") (pin "2") (pinfunction "2_2") (pintype "passive"))
      (node (ref "R34") (pin "2") (pinfunction "2_2") (pintype "passive"))
      (node (ref "R35") (pin "2") (pinfunction "2_2") (pintype "passive"))
      (node (ref "U3") (pin "2") (pinfunction "3V3_2") (pintype "passive"))
    )
    (net (code "54") (name "5V") (class "Default")
      (node (ref "C1") (pin "1") (pinfunction "1_1") (pintype "passive"))
      (node (ref "C10") (pin "2") (pinfunction "2_2") (pintype "passive"))
      (node (ref "C12") (pin "1") (pinfunction "1_1") (pintype "passive"))
      (node (ref "C15") (pin "1") (pinfunction "1_1") (pintype "passive"))
      (node (ref "C18") (pin "2") (pinfunction "2_2") (pintype "passive"))
      (node (ref "D12") (pin "2") (pinfunction "K_2") (pintype "passive"))
      (node (ref "F1") (pin "2") (pinfunction "2_2") (pintype "passive"))
      (node (ref "IC1") (pin "3") (pinfunction "V-IN_3") (pintype "power_in"))
      (node (ref "IC2") (pin "14") (pinfunction "VCC_14") (pintype "passive"))
      (node (ref "IC4") (pin "8") (pinfunction "VCC_8") (pintype "passive"))
      (node (ref "J2") (pin "3") (pinfunction "3_3") (pintype "passive"))
      (node (ref "R1") (pin "1") (pinfunction "1_1") (pintype "passive"))
      (node (ref "R12") (pin "1") (pinfunction "1_1") (pintype "passive"))
      (node (ref "R13") (pin "2") (pinfunction "2_2") (pintype "passive"))
      (node (ref "R27") (pin "2") (pinfunction "2_2") (pintype "passive"))
      (node (ref "R28") (pin "2") (pinfunction "2_2") (pintype "passive"))
      (node (ref "R4") (pin "1") (pinfunction "1_1") (pintype "passive"))
      (node (ref "U2") (pin "8") (pinfunction "VCC_8") (pintype "passive"))
      (node (ref "U4") (pin "1") (pinfunction "DREC_1") (pintype "passive"))
      (node (ref "U4") (pin "20") (pinfunction "VCC_20") (pintype "passive"))
    )
    (net (code "55") (name "5V_RL") (class "Default")
      (node (ref "C11") (pin "1") (pinfunction "1_1") (pintype "passive"))
      (node (ref "C2") (pin "1") (pinfunction "1_1") (pintype "passive"))
      (node (ref "D10") (pin "K") (pinfunction "K_K") (pintype "passive"))
      (node (ref "D6") (pin "K") (pinfunction "K_K") (pintype "passive"))
      (node (ref "L1") (pin "2") (pinfunction "2_2") (pintype "passive"))
      (node (ref "O1") (pin "4") (pinfunction "C_4") (pintype "passive"))
      (node (ref "O2") (pin "4") (pinfunction "C_4") (pintype "passive"))
      (node (ref "RL1") (pin "5") (pinfunction "COIL2_5") (pintype "passive"))
      (node (ref "RL2") (pin "5") (pinfunction "COIL2_5") (pintype "passive"))
    )
    (net (code "56") (name "BOOT_5V") (class "Default")
      (node (ref "C3") (pin "1") (pinfunction "1_1") (pintype "passive"))
      (node (ref "U1") (pin "1") (pinfunction "BOOT_1") (pintype "passive"))
    )
    (net (code "57") (name "GND") (class "Default")
      (node (ref "C1") (pin "2") (pinfunction "2_2") (pintype "passive"))
      (node (ref "C10") (pin "1") (pinfunction "1_1") (pintype "passive"))
      (node (ref "C11") (pin "2") (pinfunction "2_2") (pintype "passive"))
      (node (ref "C12") (pin "2") (pinfunction "2_2") (pintype "passive"))
      (node (ref "C13") (pin "1") (pinfunction "1_1") (pintype "passive"))
      (node (ref "C14") (pin "2") (pinfunction "2_2") (pintype "passive"))
      (node (ref "C15") (pin "2") (pinfunction "2_2") (pintype "passive"))
      (node (ref "C16") (pin "2") (pinfunction "2_2") (pintype "passive"))
      (node (ref "C17") (pin "1") (pinfunction "1_1") (pintype "passive"))
      (node (ref "C18") (pin "1") (pinfunction "1_1") (pintype "passive"))
      (node (ref "C19") (pin "2") (pinfunction "2_2") (pintype "passive"))
      (node (ref "C2") (pin "2") (pinfunction "2_2") (pintype "passive"))
      (node (ref "C20") (pin "2") (pinfunction "2_2") (pintype "passive"))
      (node (ref "C21") (pin "2") (pinfunction "2_2") (pintype "passive"))
      (node (ref "C22") (pin "2") (pinfunction "2_2") (pintype "passive"))
      (node (ref "C4") (pin "2") (pinfunction "2_2") (pintype "passive"))
      (node (ref "C5") (pin "2") (pinfunction "2_2") (pintype "passive"))
      (node (ref "C6") (pin "2") (pinfunction "2_2") (pintype "passive"))
      (node (ref "C7") (pin "2") (pinfunction "2_2") (pintype "passive"))
      (node (ref "C8") (pin "2") (pinfunction "2_2") (pintype "passive"))
      (node (ref "C9") (pin "1") (pinfunction "1_1") (pintype "passive"))
      (node (ref "D1") (pin "2") (pinfunction "2_2") (pintype "passive"))
      (node (ref "D11") (pin "3") (pinfunction "3_3") (pintype "passive"))
      (node (ref "D3") (pin "A") (pinfunction "A_A") (pintype "passive"))
      (node (ref "D4") (pin "2") (pinfunction "2_2") (pintype "passive"))
      (node (ref "D5") (pin "2") (pinfunction "2_2") (pintype "passive"))
      (node (ref "D8") (pin "2") (pinfunction "2_2") (pintype "passive"))
      (node (ref "D9") (pin "2") (pinfunction "2_2") (pintype "passive"))
      (node (ref "IC1") (pin "1") (pinfunction "GND_1") (pintype "power_in"))
      (node (ref "IC2") (pin "7") (pinfunction "GND_7") (pintype "passive"))
      (node (ref "IC3") (pin "1") (pinfunction "GND_1") (pintype "passive"))
      (node (ref "IC3") (pin "12") (pinfunction "GND_12") (pintype "passive"))
      (node (ref "IC3") (pin "2") (pinfunction "GND_2") (pintype "passive"))
      (node (ref "IC4") (pin "4") (pinfunction "GND_4") (pintype "passive"))
      (node (ref "IC5") (pin "7") (pinfunction "GND_7") (pintype "passive"))
      (node (ref "IC6") (pin "1") (pinfunction "C1_1") (pintype "passive"))
      (node (ref "IC6") (pin "10") (pinfunction "C3_10") (pintype "passive"))
      (node (ref "IC6") (pin "4") (pinfunction "C2_4") (pintype "passive"))
      (node (ref "IC6") (pin "7") (pinfunction "GND_7") (pintype "passive"))
      (node (ref "J1") (pin "3") (pinfunction "3_3") (pintype "passive"))
      (node (ref "J2") (pin "4") (pinfunction "4_4") (pintype "passive"))
      (node (ref "J5") (pin "1") (pinfunction "1_1") (pintype "passive"))
      (node (ref "J7") (pin "2") (pinfunction "2_2") (pintype "passive"))
      (node (ref "Mini SDCard1") (pin "6") (pinfunction "GND_6") (pintype "passive"))
      (node (ref "O1") (pin "2") (pinfunction "K_2") (pintype "passive"))
      (node (ref "O2") (pin "2") (pinfunction "K_2") (pintype "passive"))
      (node (ref "R10") (pin "2") (pinfunction "2_2") (pintype "passive"))
      (node (ref "R19") (pin "2") (pinfunction "2_2") (pintype "passive"))
      (node (ref "R38") (pin "1") (pinfunction "1_1") (pintype "passive"))
      (node (ref "SW1") (pin "2") (pinfunction "2_2") (pintype "passive"))
      (node (ref "SW1") (pin "3") (pinfunction "3_3") (pintype "passive"))
      (node (ref "SW2") (pin "2") (pinfunction "2_2") (pintype "passive"))
      (node (ref "SW2") (pin "3") (pinfunction "3_3") (pintype "passive"))
      (node (ref "T1") (pin "2") (pinfunction "E_2") (pintype "passive"))
      (node (ref "T2") (pin "2") (pinfunction "E_2") (pintype "passive"))
      (node (ref "U1") (pin "6") (pinfunction "GND_6") (pintype "passive"))
      (node (ref "U1") (pin "9") (pinfunction "PGND_9") (pintype "passive"))
      (node (ref "U2") (pin "5") (pinfunction "GND_5") (pintype "passive"))
      (node (ref "U3") (pin "1") (pinfunction "GND_1") (pintype "passive"))
      (node (ref "U3") (pin "15") (pinfunction "GND_15") (pintype "passive"))
      (node (ref "U3") (pin "38") (pinfunction "GND_38") (pintype "passive"))
      (node (ref "U3") (pin "39") (pinfunction "P_GND_39") (pintype "passive"))
      (node (ref "U4") (pin "10") (pinfunction "GND_10") (pintype "passive"))
      (node (ref "U4") (pin "19") (pinfunction "~{O_EN}_19") (pintype "passive"))
    )
    (net (code "58") (name "Net-(C4-Pad1)") (class "Default")
      (node (ref "C4") (pin "1") (pinfunction "1_1") (pintype "passive"))
      (node (ref "F1") (pin "1") (pinfunction "1_1") (pintype "passive"))
      (node (ref "L2") (pin "2") (pinfunction "2_2") (pintype "passive"))
    )
    (net (code "59") (name "Net-(C5-Pad1)") (class "Default")
      (node (ref "C5") (pin "1") (pinfunction "1_1") (pintype "passive"))
      (node (ref "L1") (pin "1") (pinfunction "1_1") (pintype "passive"))
      (node (ref "L2") (pin "1") (pinfunction "1_1") (pintype "passive"))
      (node (ref "L3") (pin "2") (pinfunction "2_2") (pintype "passive"))
      (node (ref "R3") (pin "1") (pinfunction "1_1") (pintype "passive"))
    )
    (net (code "60") (name "Net-(D1-Pad1)") (class "Default")
      (node (ref "D1") (pin "1") (pinfunction "1_1") (pintype "passive"))
      (node (ref "R2") (pin "1") (pinfunction "1_1") (pintype "passive"))
    )
    (net (code "61") (name "Net-(D2-K)") (class "Default")
      (node (ref "C6") (pin "1") (pinfunction "1_1") (pintype "passive"))
      (node (ref "C7") (pin "1") (pinfunction "1_1") (pintype "passive"))
      (node (ref "D2") (pin "2") (pinfunction "K_2") (pintype "passive"))
      (node (ref "U1") (pin "7") (pinfunction "VIN_7") (pintype "passive"))
    )
    (net (code "62") (name "Net-(D4-Pad1)") (class "Default")
      (node (ref "D4") (pin "1") (pinfunction "1_1") (pintype "passive"))
      (node (ref "R5") (pin "1") (pinfunction "1_1") (pintype "passive"))
    )
    (net (code "63") (name "Net-(D5-Pad1)") (class "Default")
      (node (ref "D5") (pin "1") (pinfunction "1_1") (pintype "passive"))
      (node (ref "R8") (pin "1") (pinfunction "1_1") (pintype "passive"))
    )
    (net (code "64") (name "Net-(D7-A)") (class "Default")
      (node (ref "C8") (pin "1") (pinfunction "1_1") (pintype "passive"))
      (node (ref "D7") (pin "1") (pinfunction "A_1") (pintype "passive"))
      (node (ref "IC2") (pin "13") (pinfunction "6A_13") (pintype "passive"))
      (node (ref "R7") (pin "1") (pinfunction "1_1") (pintype "passive"))
    )
    (net (code "65") (name "Net-(D8-Pad1)") (class "Default")
      (node (ref "D8") (pin "1") (pinfunction "1_1") (pintype "passive"))
      (node (ref "R4") (pin "2") (pinfunction "2_2") (pintype "passive"))
    )
    (net (code "66") (name "Net-(D9-Pad1)") (class "Default")
      (node (ref "D9") (pin "1") (pinfunction "1_1") (pintype "passive"))
      (node (ref "R15") (pin "1") (pinfunction "1_1") (pintype "passive"))
    )
    (net (code "67") (name "Net-(D13-Pad1)") (class "Default")
      (node (ref "D13") (pin "1") (pinfunction "1_1") (pintype "passive"))
      (node (ref "R30") (pin "1") (pinfunction "1_1") (pintype "passive"))
    )
    (net (code "68") (name "Net-(D14-Pad1)") (class "Default")
      (node (ref "D14") (pin "1") (pinfunction "1_1") (pintype "passive"))
      (node (ref "R31") (pin "1") (pinfunction "1_1") (pintype "passive"))
    )
    (net (code "69") (name "Net-(D15-Pad1)") (class "Default")
      (node (ref "D15") (pin "1") (pinfunction "1_1") (pintype "passive"))
      (node (ref "R32") (pin "1") (pinfunction "1_1") (pintype "passive"))
    )
    (net (code "70") (name "Net-(IC2-3Y)") (class "Default")
      (node (ref "IC2") (pin "6") (pinfunction "3Y_6") (pintype "passive"))
      (node (ref "R8") (pin "2") (pinfunction "2_2") (pintype "passive"))
    )
    (net (code "71") (name "Net-(IC4-X1)") (class "Default")
      (node (ref "Cr1") (pin "2") (pinfunction "2_2") (pintype "passive"))
      (node (ref "IC4") (pin "1") (pinfunction "X1_1") (pintype "passive"))
    )
    (net (code "72") (name "Net-(IC4-X2)") (class "Default")
      (node (ref "Cr1") (pin "1") (pinfunction "1_1") (pintype "passive"))
      (node (ref "IC4") (pin "2") (pinfunction "X2_2") (pintype "passive"))
    )
    (net (code "73") (name "Net-(IC6-A1)") (class "Default")
      (node (ref "IC6") (pin "2") (pinfunction "A1_2") (pintype "passive"))
      (node (ref "R29") (pin "1") (pinfunction "1_1") (pintype "passive"))
    )
    (net (code "74") (name "Net-(IC6-A2)") (class "Default")
      (node (ref "IC6") (pin "5") (pinfunction "A2_5") (pintype "passive"))
      (node (ref "R36") (pin "1") (pinfunction "1_1") (pintype "passive"))
    )
    (net (code "75") (name "Net-(IC6-A3)") (class "Default")
      (node (ref "IC6") (pin "9") (pinfunction "A3_9") (pintype "passive"))
      (node (ref "R37") (pin "2") (pinfunction "2_2") (pintype "passive"))
    )
    (net (code "76") (name "Net-(O1-A)") (class "Default")
      (node (ref "O1") (pin "1") (pinfunction "A_1") (pintype "passive"))
      (node (ref "R6") (pin "1") (pinfunction "1_1") (pintype "passive"))
    )
    (net (code "77") (name "Net-(O1-E)") (class "Default")
      (node (ref "O1") (pin "3") (pinfunction "E_3") (pintype "passive"))
      (node (ref "R11") (pin "2") (pinfunction "2_2") (pintype "passive"))
    )
    (net (code "78") (name "Net-(O2-A)") (class "Default")
      (node (ref "O2") (pin "1") (pinfunction "A_1") (pintype "passive"))
      (node (ref "R16") (pin "1") (pinfunction "1_1") (pintype "passive"))
    )
    (net (code "79") (name "Net-(O2-E)") (class "Default")
      (node (ref "O2") (pin "3") (pinfunction "E_3") (pintype "passive"))
      (node (ref "R20") (pin "2") (pinfunction "2_2") (pintype "passive"))
    )
    (net (code "80") (name "Net-(R10-Pad1)") (class "Default")
      (node (ref "R10") (pin "1") (pinfunction "1_1") (pintype "passive"))
      (node (ref "R9") (pin "2") (pinfunction "2_2") (pintype "passive"))
    )
    (net (code "81") (name "Net-(RL1-COIL1)") (class "Default")
      (node (ref "D6") (pin "A") (pinfunction "A_A") (pintype "passive"))
      (node (ref "RL1") (pin "2") (pinfunction "COIL1_2") (pintype "passive"))
      (node (ref "T1") (pin "3") (pinfunction "C_3") (pintype "passive"))
    )
    (net (code "82") (name "Net-(RL2-COIL1)") (class "Default")
      (node (ref "D10") (pin "A") (pinfunction "A_A") (pintype "passive"))
      (node (ref "RL2") (pin "2") (pinfunction "COIL1_2") (pintype "passive"))
      (node (ref "T2") (pin "3") (pinfunction "C_3") (pintype "passive"))
    )
    (net (code "83") (name "Net-(T1-B)") (class "Default")
      (node (ref "R11") (pin "1") (pinfunction "1_1") (pintype "passive"))
      (node (ref "T1") (pin "1") (pinfunction "B_1") (pintype "passive"))
    )
    (net (code "84") (name "Net-(T2-B)") (class "Default")
      (node (ref "R20") (pin "1") (pinfunction "1_1") (pintype "passive"))
      (node (ref "T2") (pin "1") (pinfunction "B_1") (pintype "passive"))
    )
    (net (code "85") (name "Net-(U1-PH)") (class "Default")
      (node (ref "C3") (pin "2") (pinfunction "2_2") (pintype "passive"))
      (node (ref "D3") (pin "K") (pinfunction "K_K") (pintype "passive"))
      (node (ref "L3") (pin "1") (pinfunction "1_1") (pintype "passive"))
      (node (ref "U1") (pin "8") (pinfunction "PH_8") (pintype "passive"))
    )
    (net (code "86") (name "Net-(U2-A)") (class "Default")
      (node (ref "R14") (pin "2") (pinfunction "2_2") (pintype "passive"))
      (node (ref "U2") (pin "6") (pinfunction "A_6") (pintype "passive"))
    )
    (net (code "87") (name "Net-(U2-B)") (class "Default")
      (node (ref "R18") (pin "2") (pinfunction "2_2") (pintype "passive"))
      (node (ref "U2") (pin "7") (pinfunction "B_7") (pintype "passive"))
    )
    (net (code "88") (name "unconnected-(IC3-INT-Pad6)") (class "Default")
      (node (ref "IC3") (pin "6") (pinfunction "INT_6") (pintype "passive+no_connect"))
    )
    (net (code "89") (name "unconnected-(IC3-NC-Pad9)") (class "Default")
      (node (ref "IC3") (pin "9") (pinfunction "NC_9") (pintype "passive+no_connect"))
    )
    (net (code "90") (name "unconnected-(IC4-SQW{slash}OUT-Pad7)") (class "Default")
      (node (ref "IC4") (pin "7") (pinfunction "SQW/OUT_7") (pintype "passive+no_connect"))
    )
    (net (code "91") (name "unconnected-(IC5-4A-Pad9)") (class "Default")
      (node (ref "IC5") (pin "9") (pinfunction "4A_9") (pintype "passive+no_connect"))
    )
    (net (code "92") (name "unconnected-(IC5-4Y-Pad8)") (class "Default")
      (node (ref "IC5") (pin "8") (pinfunction "4Y_8") (pintype "passive+no_connect"))
    )
    (net (code "93") (name "unconnected-(IC5-5A-Pad11)") (class "Default")
      (node (ref "IC5") (pin "11") (pinfunction "5A_11") (pintype "passive+no_connect"))
    )
    (net (code "94") (name "unconnected-(IC5-5Y-Pad10)") (class "Default")
      (node (ref "IC5") (pin "10") (pinfunction "5Y_10") (pintype "passive+no_connect"))
    )
    (net (code "95") (name "unconnected-(IC5-6A-Pad13)") (class "Default")
      (node (ref "IC5") (pin "13") (pinfunction "6A_13") (pintype "passive+no_connect"))
    )
    (net (code "96") (name "unconnected-(IC5-6Y-Pad12)") (class "Default")
      (node (ref "IC5") (pin "12") (pinfunction "6Y_12") (pintype "passive+no_connect"))
    )
    (net (code "97") (name "unconnected-(IC6-A4-Pad12)") (class "Default")
      (node (ref "IC6") (pin "12") (pinfunction "A4_12") (pintype "passive+no_connect"))
    )
    (net (code "98") (name "unconnected-(IC6-C4-Pad13)") (class "Default")
      (node (ref "IC6") (pin "13") (pinfunction "C4_13") (pintype "passive+no_connect"))
    )
    (net (code "99") (name "unconnected-(IC6-Y4-Pad11)") (class "Default")
      (node (ref "IC6") (pin "11") (pinfunction "Y4_11") (pintype "passive+no_connect"))
    )
    (net (code "100") (name "unconnected-(Mini SDCard1-NC-Pad1)") (class "Default")
      (node (ref "Mini SDCard1") (pin "1") (pinfunction "NC_1") (pintype "passive+no_connect"))
    )
    (net (code "101") (name "unconnected-(Mini SDCard1-NC-Pad8)") (class "Default")
      (node (ref "Mini SDCard1") (pin "8") (pinfunction "NC_8") (pintype "passive+no_connect"))
    )
    (net (code "102") (name "unconnected-(U1-ENA-Pad5)") (class "Default")
      (node (ref "U1") (pin "5") (pinfunction "ENA_5") (pintype "passive+no_connect"))
    )
    (net (code "103") (name "unconnected-(U1-NC-Pad2)") (class "Default")
      (node (ref "U1") (pin "2") (pinfunction "NC_2") (pintype "passive+no_connect"))
    )
    (net (code "104") (name "unconnected-(U1-NC-Pad3)") (class "Default")
      (node (ref "U1") (pin "3") (pinfunction "NC_3") (pintype "passive+no_connect"))
    )
    (net (code "105") (name "unconnected-(U3-IO2-Pad24)") (class "Default")
      (node (ref "U3") (pin "24") (pinfunction "IO2_24") (pintype "passive+no_connect"))
    )
    (net (code "106") (name "unconnected-(U3-IO6{slash}CLK-Pad20)") (class "Default")
      (node (ref "U3") (pin "20") (pinfunction "IO6/CLK_20") (pintype "passive"))
    )
    (net (code "107") (name "unconnected-(U3-IO7{slash}SD0-Pad21)") (class "Default")
      (node (ref "U3") (pin "21") (pinfunction "IO7/SD0_21") (pintype "passive"))
    )
    (net (code "108") (name "unconnected-(U3-IO8{slash}SD1-Pad22)") (class "Default")
      (node (ref "U3") (pin "22") (pinfunction "IO8/SD1_22") (pintype "passive"))
    )
    (net (code "109") (name "unconnected-(U3-IO9{slash}SD2-Pad17)") (class "Default")
      (node (ref "U3") (pin "17") (pinfunction "IO9/SD2_17") (pintype "passive"))
    )
    (net (code "110") (name "unconnected-(U3-IO10{slash}SD3-Pad18)") (class "Default")
      (node (ref "U3") (pin "18") (pinfunction "IO10/SD3_18") (pintype "passive"))
    )
    (net (code "111") (name "unconnected-(U3-IO11{slash}CMD-Pad19)") (class "Default")
      (node (ref "U3") (pin "19") (pinfunction "IO11/CMD_19") (pintype "passive"))
    )
    (net (code "112") (name "unconnected-(U3-IO12-Pad14)") (class "Default")
      (node (ref "U3") (pin "14") (pinfunction "IO12_14") (pintype "passive+no_connect"))
    )
    (net (code "113") (name "unconnected-(U3-IO13-Pad16)") (class "Default")
      (node (ref "U3") (pin "16") (pinfunction "IO13_16") (pintype "passive+no_connect"))
    )
    (net (code "114") (name "unconnected-(U3-IO17-Pad28)") (class "Default")
      (node (ref "U3") (pin "28") (pinfunction "IO17_28") (pintype "passive+no_connect"))
    )
    (net (code "115") (name "unconnected-(U3-IO39{slash}SENSOR_VN-Pad5)") (class "Default")
      (node (ref "U3") (pin "5") (pinfunction "IO39/SENSOR_VN_5") (pintype "passive+no_connect"))
    )
    (net (code "116") (name "unconnected-(U3-NC-Pad32)") (class "Default")
      (node (ref "U3") (pin "32") (pinfunction "NC_32") (pintype "passive"))
    )
    (net (code "117") (name "unconnected-(U4-A5-Pad6)") (class "Default")
      (node (ref "U4") (pin "6") (pinfunction "A5_6") (pintype "passive+no_connect"))
    )
    (net (code "118") (name "unconnected-(U4-A6-Pad7)") (class "Default")
      (node (ref "U4") (pin "7") (pinfunction "A6_7") (pintype "passive+no_connect"))
    )
    (net (code "119") (name "unconnected-(U4-A7-Pad8)") (class "Default")
      (node (ref "U4") (pin "8") (pinfunction "A7_8") (pintype "passive+no_connect"))
    )
    (net (code "120") (name "unconnected-(U4-A8-Pad9)") (class "Default")
      (node (ref "U4") (pin "9") (pinfunction "A8_9") (pintype "passive+no_connect"))
    )
    (net (code "121") (name "unconnected-(U4-B5-Pad14)") (class "Default")
      (node (ref "U4") (pin "14") (pinfunction "B5_14") (pintype "passive+no_connect"))
    )
    (net (code "122") (name "unconnected-(U4-B6-Pad13)") (class "Default")
      (node (ref "U4") (pin "13") (pinfunction "B6_13") (pintype "passive+no_connect"))
    )
    (net (code "123") (name "unconnected-(U4-B7-Pad12)") (class "Default")
      (node (ref "U4") (pin "12") (pinfunction "B7_12") (pintype "passive+no_connect"))
    )
    (net (code "124") (name "unconnected-(U4-B8-Pad11)") (class "Default")
      (node (ref "U4") (pin "11") (pinfunction "B8_11") (pintype "passive+no_connect"))
    )
  )
)
